# KEY.net
KiCad netlist of a schematic drawn in Altium Designer
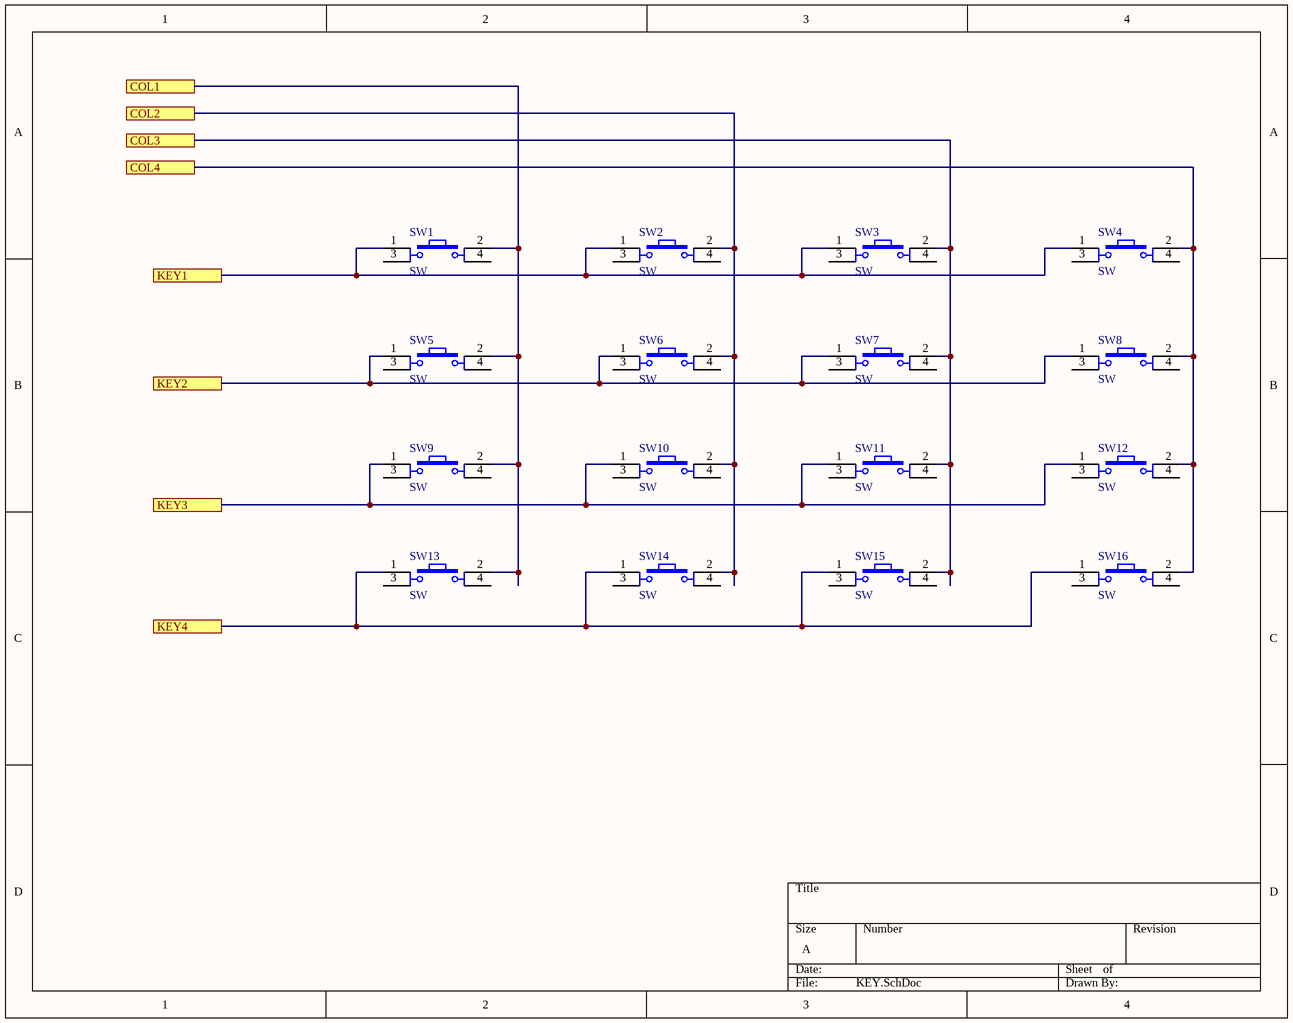
[diagram p0: KEY.SchDoc]

(export (version "E")
  (design (tool "Eeschema 10.0.6"))
  (components
    (comp (ref "SW1")
      (value "SW")
      (footprint "SW4B_SMD")
      (description "Switch button 4 pin")
      (libsource (lib "nhan") (part "SW4"))
    )
    (comp (ref "SW2")
      (value "SW")
      (footprint "SW4B_SMD")
      (description "Switch button 4 pin")
      (libsource (lib "nhan") (part "SW4"))
    )
    (comp (ref "SW3")
      (value "SW")
      (footprint "SW4B_SMD")
      (description "Switch button 4 pin")
      (libsource (lib "nhan") (part "SW4"))
    )
    (comp (ref "SW4")
      (value "SW")
      (footprint "SW4B_SMD")
      (description "Switch button 4 pin")
      (libsource (lib "nhan") (part "SW4"))
    )
    (comp (ref "SW5")
      (value "SW")
      (footprint "SW4B_SMD")
      (description "Switch button 4 pin")
      (libsource (lib "nhan") (part "SW4"))
    )
    (comp (ref "SW6")
      (value "SW")
      (footprint "SW4B_SMD")
      (description "Switch button 4 pin")
      (libsource (lib "nhan") (part "SW4"))
    )
    (comp (ref "SW7")
      (value "SW")
      (footprint "SW4B_SMD")
      (description "Switch button 4 pin")
      (libsource (lib "nhan") (part "SW4"))
    )
    (comp (ref "SW8")
      (value "SW")
      (footprint "SW4B_SMD")
      (description "Switch button 4 pin")
      (libsource (lib "nhan") (part "SW4"))
    )
    (comp (ref "SW9")
      (value "SW")
      (footprint "SW4B_SMD")
      (description "Switch button 4 pin")
      (libsource (lib "nhan") (part "SW4"))
    )
    (comp (ref "SW10")
      (value "SW")
      (footprint "SW4B_SMD")
      (description "Switch button 4 pin")
      (libsource (lib "nhan") (part "SW4"))
    )
    (comp (ref "SW11")
      (value "SW")
      (footprint "SW4B_SMD")
      (description "Switch button 4 pin")
      (libsource (lib "nhan") (part "SW4"))
    )
    (comp (ref "SW12")
      (value "SW")
      (footprint "SW4B_SMD")
      (description "Switch button 4 pin")
      (libsource (lib "nhan") (part "SW4"))
    )
    (comp (ref "SW13")
      (value "SW")
      (footprint "SW4B_SMD")
      (description "Switch button 4 pin")
      (libsource (lib "nhan") (part "SW4"))
    )
    (comp (ref "SW14")
      (value "SW")
      (footprint "SW4B_SMD")
      (description "Switch button 4 pin")
      (libsource (lib "nhan") (part "SW4"))
    )
    (comp (ref "SW15")
      (value "SW")
      (footprint "SW4B_SMD")
      (description "Switch button 4 pin")
      (libsource (lib "nhan") (part "SW4"))
    )
    (comp (ref "SW16")
      (value "SW")
      (footprint "SW4B_SMD")
      (description "Switch button 4 pin")
      (libsource (lib "nhan") (part "SW4"))
    )
  )
  (nets
    (net (code "1") (name "/COL1") (class "Default")
      (node (ref "SW1") (pin "2") (pintype "passive"))
      (node (ref "SW13") (pin "2") (pintype "passive"))
      (node (ref "SW5") (pin "2") (pintype "passive"))
      (node (ref "SW9") (pin "2") (pintype "passive"))
    )
    (net (code "2") (name "/COL2") (class "Default")
      (node (ref "SW10") (pin "2") (pintype "passive"))
      (node (ref "SW14") (pin "2") (pintype "passive"))
      (node (ref "SW2") (pin "2") (pintype "passive"))
      (node (ref "SW6") (pin "2") (pintype "passive"))
    )
    (net (code "3") (name "/COL3") (class "Default")
      (node (ref "SW11") (pin "2") (pintype "passive"))
      (node (ref "SW15") (pin "2") (pintype "passive"))
      (node (ref "SW3") (pin "2") (pintype "passive"))
      (node (ref "SW7") (pin "2") (pintype "passive"))
    )
    (net (code "4") (name "/COL4") (class "Default")
      (node (ref "SW12") (pin "2") (pintype "passive"))
      (node (ref "SW16") (pin "2") (pintype "passive"))
      (node (ref "SW4") (pin "2") (pintype "passive"))
      (node (ref "SW8") (pin "2") (pintype "passive"))
    )
    (net (code "5") (name "/KEY1") (class "Default")
      (node (ref "SW1") (pin "1") (pintype "passive"))
      (node (ref "SW2") (pin "1") (pintype "passive"))
      (node (ref "SW3") (pin "1") (pintype "passive"))
      (node (ref "SW4") (pin "1") (pintype "passive"))
    )
    (net (code "6") (name "/KEY2") (class "Default")
      (node (ref "SW5") (pin "1") (pintype "passive"))
      (node (ref "SW6") (pin "1") (pintype "passive"))
      (node (ref "SW7") (pin "1") (pintype "passive"))
      (node (ref "SW8") (pin "1") (pintype "passive"))
    )
    (net (code "7") (name "/KEY3") (class "Default")
      (node (ref "SW10") (pin "1") (pintype "passive"))
      (node (ref "SW11") (pin "1") (pintype "passive"))
      (node (ref "SW12") (pin "1") (pintype "passive"))
      (node (ref "SW9") (pin "1") (pintype "passive"))
    )
    (net (code "8") (name "/KEY4") (class "Default")
      (node (ref "SW13") (pin "1") (pintype "passive"))
      (node (ref "SW14") (pin "1") (pintype "passive"))
      (node (ref "SW15") (pin "1") (pintype "passive"))
      (node (ref "SW16") (pin "1") (pintype "passive"))
    )
    (net (code "9") (name "unconnected-(SW1-Pad3)") (class "Default")
      (node (ref "SW1") (pin "3") (pintype "passive"))
    )
    (net (code "10") (name "unconnected-(SW1-Pad4)") (class "Default")
      (node (ref "SW1") (pin "4") (pintype "passive"))
    )
    (net (code "11") (name "unconnected-(SW2-Pad3)") (class "Default")
      (node (ref "SW2") (pin "3") (pintype "passive"))
    )
    (net (code "12") (name "unconnected-(SW2-Pad4)") (class "Default")
      (node (ref "SW2") (pin "4") (pintype "passive"))
    )
    (net (code "13") (name "unconnected-(SW3-Pad3)") (class "Default")
      (node (ref "SW3") (pin "3") (pintype "passive"))
    )
    (net (code "14") (name "unconnected-(SW3-Pad4)") (class "Default")
      (node (ref "SW3") (pin "4") (pintype "passive"))
    )
    (net (code "15") (name "unconnected-(SW4-Pad3)") (class "Default")
      (node (ref "SW4") (pin "3") (pintype "passive"))
    )
    (net (code "16") (name "unconnected-(SW4-Pad4)") (class "Default")
      (node (ref "SW4") (pin "4") (pintype "passive"))
    )
    (net (code "17") (name "unconnected-(SW5-Pad3)") (class "Default")
      (node (ref "SW5") (pin "3") (pintype "passive"))
    )
    (net (code "18") (name "unconnected-(SW5-Pad4)") (class "Default")
      (node (ref "SW5") (pin "4") (pintype "passive"))
    )
    (net (code "19") (name "unconnected-(SW6-Pad3)") (class "Default")
      (node (ref "SW6") (pin "3") (pintype "passive"))
    )
    (net (code "20") (name "unconnected-(SW6-Pad4)") (class "Default")
      (node (ref "SW6") (pin "4") (pintype "passive"))
    )
    (net (code "21") (name "unconnected-(SW7-Pad3)") (class "Default")
      (node (ref "SW7") (pin "3") (pintype "passive"))
    )
    (net (code "22") (name "unconnected-(SW7-Pad4)") (class "Default")
      (node (ref "SW7") (pin "4") (pintype "passive"))
    )
    (net (code "23") (name "unconnected-(SW8-Pad3)") (class "Default")
      (node (ref "SW8") (pin "3") (pintype "passive"))
    )
    (net (code "24") (name "unconnected-(SW8-Pad4)") (class "Default")
      (node (ref "SW8") (pin "4") (pintype "passive"))
    )
    (net (code "25") (name "unconnected-(SW9-Pad3)") (class "Default")
      (node (ref "SW9") (pin "3") (pintype "passive"))
    )
    (net (code "26") (name "unconnected-(SW9-Pad4)") (class "Default")
      (node (ref "SW9") (pin "4") (pintype "passive"))
    )
    (net (code "27") (name "unconnected-(SW10-Pad3)") (class "Default")
      (node (ref "SW10") (pin "3") (pintype "passive"))
    )
    (net (code "28") (name "unconnected-(SW10-Pad4)") (class "Default")
      (node (ref "SW10") (pin "4") (pintype "passive"))
    )
    (net (code "29") (name "unconnected-(SW11-Pad3)") (class "Default")
      (node (ref "SW11") (pin "3") (pintype "passive"))
    )
    (net (code "30") (name "unconnected-(SW11-Pad4)") (class "Default")
      (node (ref "SW11") (pin "4") (pintype "passive"))
    )
    (net (code "31") (name "unconnected-(SW12-Pad3)") (class "Default")
      (node (ref "SW12") (pin "3") (pintype "passive"))
    )
    (net (code "32") (name "unconnected-(SW12-Pad4)") (class "Default")
      (node (ref "SW12") (pin "4") (pintype "passive"))
    )
    (net (code "33") (name "unconnected-(SW13-Pad3)") (class "Default")
      (node (ref "SW13") (pin "3") (pintype "passive"))
    )
    (net (code "34") (name "unconnected-(SW13-Pad4)") (class "Default")
      (node (ref "SW13") (pin "4") (pintype "passive"))
    )
    (net (code "35") (name "unconnected-(SW14-Pad3)") (class "Default")
      (node (ref "SW14") (pin "3") (pintype "passive"))
    )
    (net (code "36") (name "unconnected-(SW14-Pad4)") (class "Default")
      (node (ref "SW14") (pin "4") (pintype "passive"))
    )
    (net (code "37") (name "unconnected-(SW15-Pad3)") (class "Default")
      (node (ref "SW15") (pin "3") (pintype "passive"))
    )
    (net (code "38") (name "unconnected-(SW15-Pad4)") (class "Default")
      (node (ref "SW15") (pin "4") (pintype "passive"))
    )
    (net (code "39") (name "unconnected-(SW16-Pad3)") (class "Default")
      (node (ref "SW16") (pin "3") (pintype "passive"))
    )
    (net (code "40") (name "unconnected-(SW16-Pad4)") (class "Default")
      (node (ref "SW16") (pin "4") (pintype "passive"))
    )
  )
)
